# ESP_32_S3_Wroom.net
KiCad netlist of a schematic drawn in Altium Designer
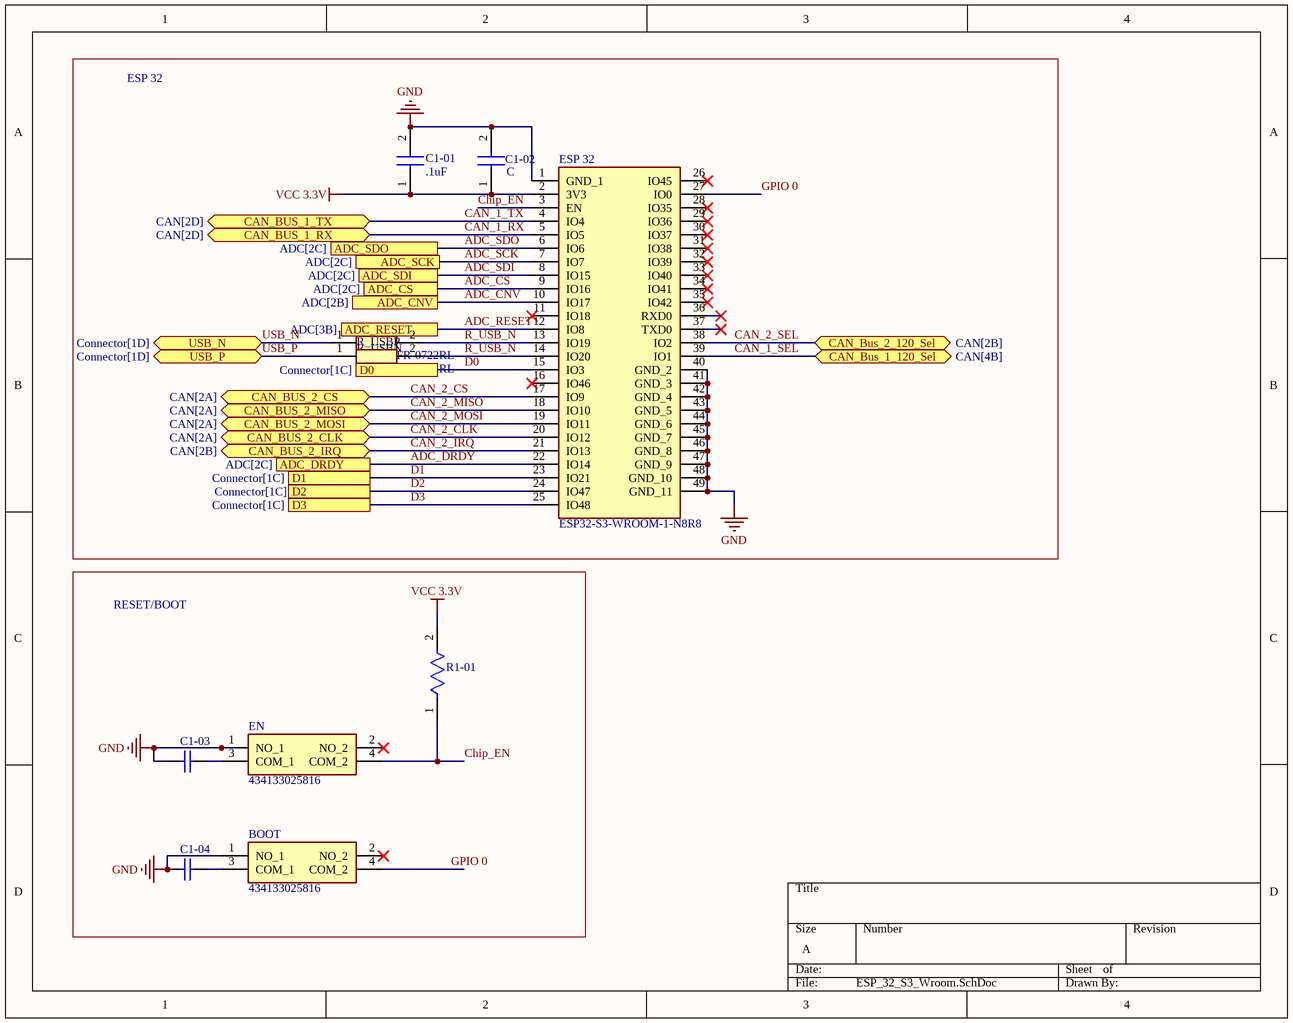
[diagram p0: ESP_32_S3_Wroom.SchDoc]

(export (version "E")
  (design (tool "Eeschema 10.0.6"))
  (components
    (comp (ref "BOOT")
      (value "434133025816")
      (footprint "SamacSys:434133025816")
      (description "Switch")
      (fields (field (name "MOUSER PART NUMBER") "710-434133025816"))
      (libsource (lib "*") (part "434133025816"))
    )
    (comp (ref "C1-01")
      (value ".1uF")
      (footprint "SamacSys:CAPC2012X95N")
      (description "Capacitor")
      (fields
        (field (name "MANUFACTURER_PART_NUMBER") "CL21B104KBCNNNC")
        (field (name "MOUSER PART NUMBER") "187-CL21B104KBCNNNC")
      )
      (libsource (lib "*") (part "CL21B104KBCNNNC"))
    )
    (comp (ref "C1-02")
      (value "C")
      (footprint "SamacSys:CAPC2012X145N")
      (description "Capacitor")
      (fields
        (field (name "MANUFACTURER_PART_NUMBER") "CL21A226MAYNNNE")
        (field (name "MOUSER PART NUMBER") "187-CL21A226MAYNNNE")
      )
      (libsource (lib "*") (part "CL21A226MAYNNNE"))
    )
    (comp (ref "C1-03")
      (value "VJ0805Y393KXXPW1BC")
      (footprint "CAPC2013X145X50ML20T20")
      (fields (field (name "MANUFACTURER") "Vitramon"))
      (libsource (lib "Altium Content Vault") (part "CAP"))
    )
    (comp (ref "C1-04")
      (value "VJ0805Y393KXXPW1BC")
      (footprint "CAPC2013X145X50ML20T20")
      (fields (field (name "MANUFACTURER") "Vitramon"))
      (libsource (lib "Altium Content Vault") (part "CAP"))
    )
    (comp (ref "EN")
      (value "434133025816")
      (footprint "SamacSys:434133025816")
      (description "Switch")
      (fields (field (name "MOUSER PART NUMBER") "710-434133025816"))
      (libsource (lib "*") (part "434133025816"))
    )
    (comp (ref "ESP 32")
      (value "ESP32-S3-WROOM-1-N8R8")
      (footprint "SamacSys:ESP32S3WROOM1N8R8")
      (description "Integrated Circuit")
      (fields (field (name "MOUSER PART NUMBER") "356-EP32S3WROOM1N8R8"))
      (libsource (lib "SamacSys") (part "ESP32-S3-WROOM-1-N8R8"))
    )
    (comp (ref "R1-01")
      (value "CRGH0805F10K")
      (footprint "FP-CRGH0805-IPC_C")
      (description "RES SMD 10K OHM 1% 1/3W 0805")
      (fields (field (name "TOLERANCE") "1%") (field (name "MANUFACTURER") "TE Connectivity"))
      (libsource (lib "Altium Content Vault") (part "1029c3af85768c4190bb7ad29bc67b5"))
    )
    (comp (ref "R_USBN")
      (value "RC0402FR-0722RL")
      (footprint "SamacSys:RESC1005X40N")
      (description "Resistor")
      (fields (field (name "MOUSER PART NUMBER") "603-RC0402FR-0722RL"))
      (libsource (lib "*") (part "RC0402FR-0722RL"))
    )
    (comp (ref "R_USBP")
      (value "RC0402FR-0722RL")
      (footprint "SamacSys:RESC1005X40N")
      (description "Resistor")
      (fields (field (name "MOUSER PART NUMBER") "603-RC0402FR-0722RL"))
      (libsource (lib "*") (part "RC0402FR-0722RL"))
    )
  )
  (nets
    (net (code "1") (name "/ADC_CNV") (class "Default")
      (node (ref "ESP 32") (pin "10") (pinfunction "IO17_10") (pintype "passive"))
    )
    (net (code "2") (name "/ADC_CS") (class "Default")
      (node (ref "ESP 32") (pin "9") (pinfunction "IO16_9") (pintype "passive"))
    )
    (net (code "3") (name "/ADC_DRDY") (class "Default")
      (node (ref "ESP 32") (pin "22") (pinfunction "IO14_22") (pintype "passive"))
    )
    (net (code "4") (name "/ADC_RESET") (class "Default")
      (node (ref "ESP 32") (pin "12") (pinfunction "IO8_12") (pintype "passive"))
    )
    (net (code "5") (name "/ADC_SCK") (class "Default")
      (node (ref "ESP 32") (pin "7") (pinfunction "IO7_7") (pintype "passive"))
    )
    (net (code "6") (name "/ADC_SDI") (class "Default")
      (node (ref "ESP 32") (pin "8") (pinfunction "IO15_8") (pintype "passive"))
    )
    (net (code "7") (name "/ADC_SDO") (class "Default")
      (node (ref "ESP 32") (pin "6") (pinfunction "IO6_6") (pintype "passive"))
    )
    (net (code "8") (name "/CAN_1_RX") (class "Default")
      (node (ref "ESP 32") (pin "5") (pinfunction "IO5_5") (pintype "passive"))
    )
    (net (code "9") (name "/CAN_1_SEL") (class "Default")
      (node (ref "ESP 32") (pin "39") (pinfunction "IO1_39") (pintype "passive"))
    )
    (net (code "10") (name "/CAN_1_TX") (class "Default")
      (node (ref "ESP 32") (pin "4") (pinfunction "IO4_4") (pintype "passive"))
    )
    (net (code "11") (name "/CAN_2_CLK") (class "Default")
      (node (ref "ESP 32") (pin "20") (pinfunction "IO12_20") (pintype "passive"))
    )
    (net (code "12") (name "/CAN_2_CS") (class "Default")
      (node (ref "ESP 32") (pin "17") (pinfunction "IO9_17") (pintype "passive"))
    )
    (net (code "13") (name "/CAN_2_IRQ") (class "Default")
      (node (ref "ESP 32") (pin "21") (pinfunction "IO13_21") (pintype "passive"))
    )
    (net (code "14") (name "/CAN_2_MISO") (class "Default")
      (node (ref "ESP 32") (pin "18") (pinfunction "IO10_18") (pintype "passive"))
    )
    (net (code "15") (name "/CAN_2_MOSI") (class "Default")
      (node (ref "ESP 32") (pin "19") (pinfunction "IO11_19") (pintype "passive"))
    )
    (net (code "16") (name "/CAN_2_SEL") (class "Default")
      (node (ref "ESP 32") (pin "38") (pinfunction "IO2_38") (pintype "passive"))
    )
    (net (code "17") (name "/Chip_EN") (class "Default")
      (node (ref "EN") (pin "4") (pinfunction "COM_2_4") (pintype "passive"))
      (node (ref "ESP 32") (pin "3") (pinfunction "EN_3") (pintype "passive"))
      (node (ref "R1-01") (pin "1") (pinfunction "1_1") (pintype "passive"))
    )
    (net (code "18") (name "/D0") (class "Default")
      (node (ref "ESP 32") (pin "15") (pinfunction "IO3_15") (pintype "passive"))
    )
    (net (code "19") (name "/D1") (class "Default")
      (node (ref "ESP 32") (pin "23") (pinfunction "IO21_23") (pintype "passive"))
    )
    (net (code "20") (name "/D2") (class "Default")
      (node (ref "ESP 32") (pin "24") (pinfunction "IO47_24") (pintype "passive"))
    )
    (net (code "21") (name "/D3") (class "Default")
      (node (ref "ESP 32") (pin "25") (pinfunction "IO48_25") (pintype "passive"))
    )
    (net (code "22") (name "/GPIO 0") (class "Default")
      (node (ref "BOOT") (pin "4") (pinfunction "COM_2_4") (pintype "passive"))
      (node (ref "ESP 32") (pin "27") (pinfunction "IO0_27") (pintype "passive"))
    )
    (net (code "23") (name "/R_USB_N") (class "Default")
      (node (ref "ESP 32") (pin "13") (pinfunction "IO19_13") (pintype "passive"))
      (node (ref "ESP 32") (pin "14") (pinfunction "IO20_14") (pintype "passive"))
      (node (ref "R_USBN") (pin "2") (pinfunction "2_2") (pintype "passive"))
      (node (ref "R_USBP") (pin "2") (pinfunction "2_2") (pintype "passive"))
    )
    (net (code "24") (name "/USB_N") (class "Default")
      (node (ref "R_USBN") (pin "1") (pinfunction "1_1") (pintype "passive"))
    )
    (net (code "25") (name "/USB_P") (class "Default")
      (node (ref "R_USBP") (pin "1") (pinfunction "1_1") (pintype "passive"))
    )
    (net (code "26") (name "GND") (class "Default")
      (node (ref "BOOT") (pin "1") (pinfunction "NO_1_1") (pintype "passive"))
      (node (ref "C1-01") (pin "2") (pinfunction "2_2") (pintype "passive"))
      (node (ref "C1-02") (pin "2") (pinfunction "2_2") (pintype "passive"))
      (node (ref "C1-03") (pin "1") (pinfunction "1_1") (pintype "passive"))
      (node (ref "C1-04") (pin "1") (pinfunction "1_1") (pintype "passive"))
      (node (ref "EN") (pin "1") (pinfunction "NO_1_1") (pintype "passive"))
      (node (ref "ESP 32") (pin "1") (pinfunction "GND_1_1") (pintype "passive"))
      (node (ref "ESP 32") (pin "40") (pinfunction "GND_2_40") (pintype "passive"))
      (node (ref "ESP 32") (pin "41") (pinfunction "GND_3_41") (pintype "passive"))
      (node (ref "ESP 32") (pin "42") (pinfunction "GND_4_42") (pintype "passive"))
      (node (ref "ESP 32") (pin "43") (pinfunction "GND_5_43") (pintype "passive"))
      (node (ref "ESP 32") (pin "44") (pinfunction "GND_6_44") (pintype "passive"))
      (node (ref "ESP 32") (pin "45") (pinfunction "GND_7_45") (pintype "passive"))
      (node (ref "ESP 32") (pin "46") (pinfunction "GND_8_46") (pintype "passive"))
      (node (ref "ESP 32") (pin "47") (pinfunction "GND_9_47") (pintype "passive"))
      (node (ref "ESP 32") (pin "48") (pinfunction "GND_10_48") (pintype "passive"))
      (node (ref "ESP 32") (pin "49") (pinfunction "GND_11_49") (pintype "passive"))
    )
    (net (code "27") (name "Net-(BOOT-COM_1)") (class "Default")
      (node (ref "BOOT") (pin "3") (pinfunction "COM_1_3") (pintype "passive"))
      (node (ref "C1-04") (pin "2") (pinfunction "2_2") (pintype "passive"))
    )
    (net (code "28") (name "Net-(EN-COM_1)") (class "Default")
      (node (ref "C1-03") (pin "2") (pinfunction "2_2") (pintype "passive"))
      (node (ref "EN") (pin "3") (pinfunction "COM_1_3") (pintype "passive"))
    )
    (net (code "29") (name "VCC 3.3V") (class "Default")
      (node (ref "C1-01") (pin "1") (pinfunction "1_1") (pintype "passive"))
      (node (ref "C1-02") (pin "1") (pinfunction "1_1") (pintype "passive"))
      (node (ref "ESP 32") (pin "2") (pinfunction "3V3_2") (pintype "passive"))
      (node (ref "R1-01") (pin "2") (pinfunction "2_2") (pintype "passive"))
    )
    (net (code "30") (name "unconnected-(BOOT-NO_2-Pad2)") (class "Default")
      (node (ref "BOOT") (pin "2") (pinfunction "NO_2_2") (pintype "passive+no_connect"))
    )
    (net (code "31") (name "unconnected-(EN-NO_2-Pad2)") (class "Default")
      (node (ref "EN") (pin "2") (pinfunction "NO_2_2") (pintype "passive+no_connect"))
    )
    (net (code "32") (name "unconnected-(ESP 32-IO18-Pad11)") (class "Default")
      (node (ref "ESP 32") (pin "11") (pinfunction "IO18_11") (pintype "passive+no_connect"))
    )
    (net (code "33") (name "unconnected-(ESP 32-IO35-Pad28)") (class "Default")
      (node (ref "ESP 32") (pin "28") (pinfunction "IO35_28") (pintype "passive+no_connect"))
    )
    (net (code "34") (name "unconnected-(ESP 32-IO36-Pad29)") (class "Default")
      (node (ref "ESP 32") (pin "29") (pinfunction "IO36_29") (pintype "passive+no_connect"))
    )
    (net (code "35") (name "unconnected-(ESP 32-IO37-Pad30)") (class "Default")
      (node (ref "ESP 32") (pin "30") (pinfunction "IO37_30") (pintype "passive+no_connect"))
    )
    (net (code "36") (name "unconnected-(ESP 32-IO38-Pad31)") (class "Default")
      (node (ref "ESP 32") (pin "31") (pinfunction "IO38_31") (pintype "passive+no_connect"))
    )
    (net (code "37") (name "unconnected-(ESP 32-IO39-Pad32)") (class "Default")
      (node (ref "ESP 32") (pin "32") (pinfunction "IO39_32") (pintype "passive+no_connect"))
    )
    (net (code "38") (name "unconnected-(ESP 32-IO40-Pad33)") (class "Default")
      (node (ref "ESP 32") (pin "33") (pinfunction "IO40_33") (pintype "passive+no_connect"))
    )
    (net (code "39") (name "unconnected-(ESP 32-IO41-Pad34)") (class "Default")
      (node (ref "ESP 32") (pin "34") (pinfunction "IO41_34") (pintype "passive+no_connect"))
    )
    (net (code "40") (name "unconnected-(ESP 32-IO42-Pad35)") (class "Default")
      (node (ref "ESP 32") (pin "35") (pinfunction "IO42_35") (pintype "passive+no_connect"))
    )
    (net (code "41") (name "unconnected-(ESP 32-IO45-Pad26)") (class "Default")
      (node (ref "ESP 32") (pin "26") (pinfunction "IO45_26") (pintype "passive+no_connect"))
    )
    (net (code "42") (name "unconnected-(ESP 32-IO46-Pad16)") (class "Default")
      (node (ref "ESP 32") (pin "16") (pinfunction "IO46_16") (pintype "passive+no_connect"))
    )
    (net (code "43") (name "unconnected-(ESP 32-RXD0-Pad36)") (class "Default")
      (node (ref "ESP 32") (pin "36") (pinfunction "RXD0_36") (pintype "passive+no_connect"))
    )
    (net (code "44") (name "unconnected-(ESP 32-TXD0-Pad37)") (class "Default")
      (node (ref "ESP 32") (pin "37") (pinfunction "TXD0_37") (pintype "passive+no_connect"))
    )
  )
)
